# FDSSD.net
KiCad netlist of a schematic drawn in EAGLE
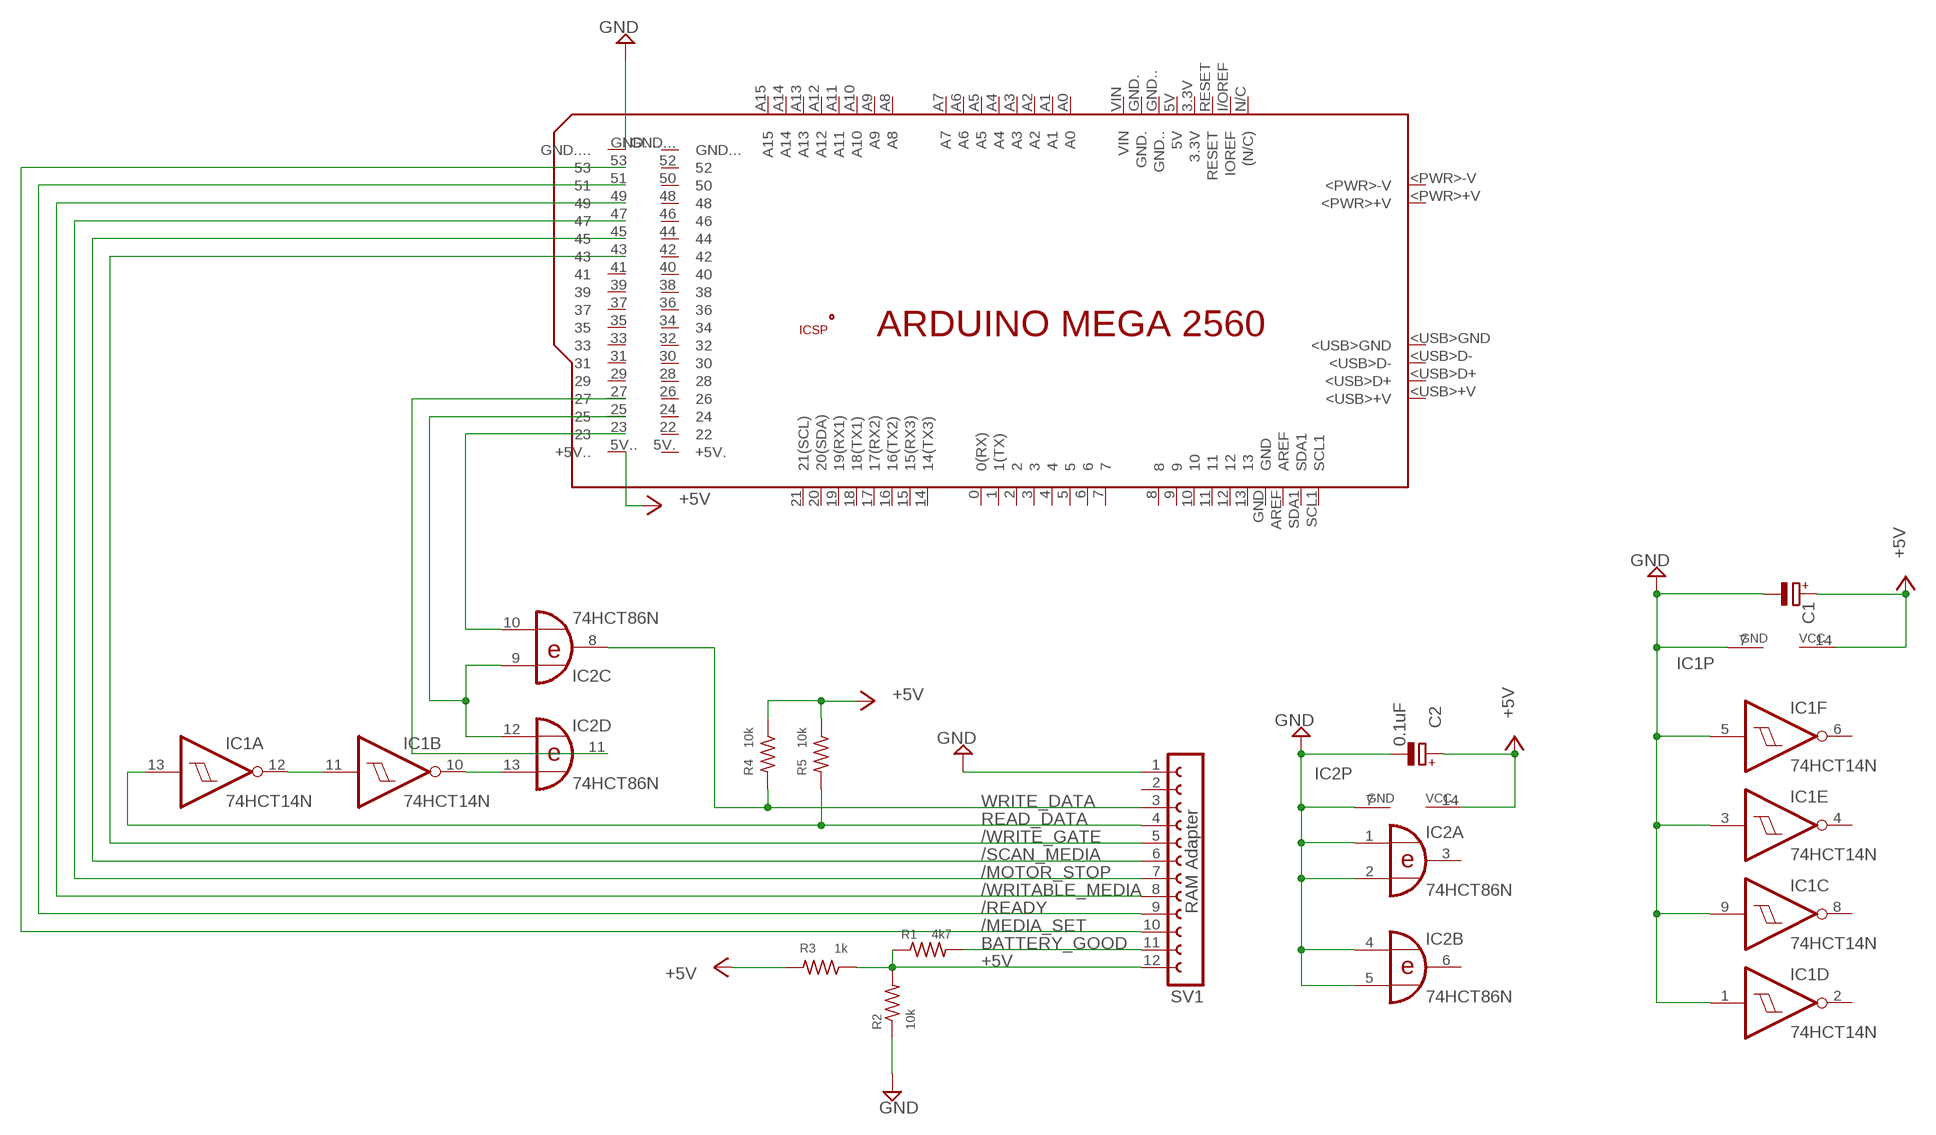
[diagram p0: schematic, sheet 1]

(export (version "E")
  (design (tool "Eeschema 10.0.6"))
  (components
    (comp (ref "C1")
      (value "CPOL-EUE2.5-5")
      (footprint "eagle-import:E2,5-5")
      (libsource (lib "eagle-import") (part "CPOL-EUE2.5-5"))
    )
    (comp (ref "C2")
      (value "0.1uF")
      (footprint "eagle-import:E2,5-5")
      (libsource (lib "eagle-import") (part "CPOL-EUE2.5-5"))
    )
    (comp (ref "IC1")
      (value "74HCT14N")
      (footprint "eagle-import:DIL14")
      (libsource (lib "eagle-import") (part "7414NHCT"))
    )
    (comp (ref "IC2")
      (value "74HCT86N")
      (footprint "eagle-import:DIL14")
      (libsource (lib "eagle-import") (part "7486NHCT"))
    )
    (comp (ref "PCB1")
      (value "ARDUINO_MEGA2560")
      (footprint "eagle-import:ARDUINO_MEGA2560")
      (libsource (lib "eagle-import") (part "ARDUINO_MEGA2560"))
    )
    (comp (ref "R1")
      (value "4k7")
      (footprint "eagle-import:0207_10")
      (libsource (lib "eagle-import") (part "R-US_0207/10"))
    )
    (comp (ref "R2")
      (value "10k")
      (footprint "eagle-import:0207_10")
      (libsource (lib "eagle-import") (part "R-US_0207/10"))
    )
    (comp (ref "R3")
      (value "1k")
      (footprint "eagle-import:0207_10")
      (libsource (lib "eagle-import") (part "R-US_0207/10"))
    )
    (comp (ref "R4")
      (value "10k")
      (footprint "eagle-import:0207_10")
      (libsource (lib "eagle-import") (part "R-US_0207/10"))
    )
    (comp (ref "R5")
      (value "10k")
      (footprint "eagle-import:0207_10")
      (libsource (lib "eagle-import") (part "R-US_0207/10"))
    )
    (comp (ref "SV1")
      (value "RAM Adapter")
      (footprint "eagle-import:FE12")
      (libsource (lib "eagle-import") (part "FE12-1"))
    )
  )
  (nets
    (net (code "1") (name "+5V") (class "Default")
      (node (ref "C1") (pin "+") (pinfunction "+_+") (pintype "passive"))
      (node (ref "C2") (pin "+") (pinfunction "+_+") (pintype "passive"))
      (node (ref "IC1") (pin "14") (pinfunction "VCC_14") (pintype "power_in"))
      (node (ref "IC2") (pin "14") (pinfunction "VCC_14") (pintype "power_in"))
      (node (ref "PCB1") (pin "5V..") (pinfunction "+5V.._5V..") (pintype "bidirectional"))
      (node (ref "R1") (pin "1") (pinfunction "1_1") (pintype "passive"))
      (node (ref "R2") (pin "2") (pinfunction "2_2") (pintype "passive"))
      (node (ref "R3") (pin "1") (pinfunction "1_1") (pintype "passive"))
      (node (ref "R3") (pin "2") (pinfunction "2_2") (pintype "passive"))
      (node (ref "R4") (pin "1") (pinfunction "1_1") (pintype "passive"))
      (node (ref "R5") (pin "1") (pinfunction "1_1") (pintype "passive"))
      (node (ref "SV1") (pin "12") (pinfunction "12_12") (pintype "passive"))
    )
    (net (code "2") (name "/BATTERY_GOOD") (class "Default")
      (node (ref "R1") (pin "2") (pinfunction "2_2") (pintype "passive"))
      (node (ref "SV1") (pin "11") (pinfunction "11_11") (pintype "passive"))
    )
    (net (code "3") (name "/READ_DATA") (class "Default")
      (node (ref "IC1") (pin "13") (pinfunction "I_13") (pintype "input"))
      (node (ref "R5") (pin "2") (pinfunction "2_2") (pintype "passive"))
      (node (ref "SV1") (pin "4") (pinfunction "4_4") (pintype "passive"))
    )
    (net (code "4") (name "/WRITE_DATA") (class "Default")
      (node (ref "IC2") (pin "8") (pinfunction "O_8") (pintype "output"))
      (node (ref "R4") (pin "2") (pinfunction "2_2") (pintype "passive"))
      (node (ref "SV1") (pin "3") (pinfunction "3_3") (pintype "passive"))
    )
    (net (code "5") (name "/{slash}MEDIA_SET") (class "Default")
      (node (ref "PCB1") (pin "53") (pinfunction "53_53") (pintype "bidirectional"))
      (node (ref "SV1") (pin "10") (pinfunction "10_10") (pintype "passive"))
    )
    (net (code "6") (name "/{slash}MOTOR_STOP") (class "Default")
      (node (ref "PCB1") (pin "47") (pinfunction "47_47") (pintype "bidirectional"))
      (node (ref "SV1") (pin "7") (pinfunction "7_7") (pintype "passive"))
    )
    (net (code "7") (name "/{slash}READY") (class "Default")
      (node (ref "PCB1") (pin "51") (pinfunction "51_51") (pintype "bidirectional"))
      (node (ref "SV1") (pin "9") (pinfunction "9_9") (pintype "passive"))
    )
    (net (code "8") (name "/{slash}SCAN_MEDIA") (class "Default")
      (node (ref "PCB1") (pin "45") (pinfunction "45_45") (pintype "bidirectional"))
      (node (ref "SV1") (pin "6") (pinfunction "6_6") (pintype "passive"))
    )
    (net (code "9") (name "/{slash}WRITABLE_MEDIA") (class "Default")
      (node (ref "PCB1") (pin "49") (pinfunction "49_49") (pintype "bidirectional"))
      (node (ref "SV1") (pin "8") (pinfunction "8_8") (pintype "passive"))
    )
    (net (code "10") (name "/{slash}WRITE_GATE") (class "Default")
      (node (ref "PCB1") (pin "43") (pinfunction "43_43") (pintype "bidirectional"))
      (node (ref "SV1") (pin "5") (pinfunction "5_5") (pintype "passive"))
    )
    (net (code "11") (name "GND") (class "Default")
      (node (ref "C1") (pin "-") (pinfunction "-_-") (pintype "passive"))
      (node (ref "C2") (pin "-") (pinfunction "-_-") (pintype "passive"))
      (node (ref "IC1") (pin "1") (pinfunction "I_1") (pintype "input"))
      (node (ref "IC1") (pin "3") (pinfunction "I_3") (pintype "input"))
      (node (ref "IC1") (pin "5") (pinfunction "I_5") (pintype "input"))
      (node (ref "IC1") (pin "7") (pinfunction "GND_7") (pintype "power_in"))
      (node (ref "IC1") (pin "9") (pinfunction "I_9") (pintype "input"))
      (node (ref "IC2") (pin "1") (pinfunction "I0_1") (pintype "input"))
      (node (ref "IC2") (pin "2") (pinfunction "I1_2") (pintype "input"))
      (node (ref "IC2") (pin "4") (pinfunction "I0_4") (pintype "input"))
      (node (ref "IC2") (pin "5") (pinfunction "I1_5") (pintype "input"))
      (node (ref "IC2") (pin "7") (pinfunction "GND_7") (pintype "power_in"))
      (node (ref "PCB1") (pin "GND....") (pinfunction "GND...._GND....") (pintype "bidirectional"))
      (node (ref "R2") (pin "1") (pinfunction "1_1") (pintype "passive"))
      (node (ref "SV1") (pin "1") (pinfunction "1_1") (pintype "passive"))
    )
    (net (code "12") (name "Net-(IC1A-O)") (class "Default")
      (node (ref "IC1") (pin "11") (pinfunction "I_11") (pintype "input"))
      (node (ref "IC1") (pin "12") (pinfunction "O_12") (pintype "output"))
    )
    (net (code "13") (name "Net-(IC1B-O)") (class "Default")
      (node (ref "IC1") (pin "10") (pinfunction "O_10") (pintype "output"))
      (node (ref "IC2") (pin "13") (pinfunction "I1_13") (pintype "input"))
    )
    (net (code "14") (name "Net-(IC2C-I0)") (class "Default")
      (node (ref "IC2") (pin "12") (pinfunction "I0_12") (pintype "input"))
      (node (ref "IC2") (pin "9") (pinfunction "I0_9") (pintype "input"))
      (node (ref "PCB1") (pin "25") (pinfunction "25_25") (pintype "bidirectional"))
    )
    (net (code "15") (name "Net-(IC2C-I1)") (class "Default")
      (node (ref "IC2") (pin "10") (pinfunction "I1_10") (pintype "input"))
      (node (ref "PCB1") (pin "23") (pinfunction "23_23") (pintype "bidirectional"))
    )
    (net (code "16") (name "Net-(IC2D-O)") (class "Default")
      (node (ref "IC2") (pin "11") (pinfunction "O_11") (pintype "output"))
      (node (ref "PCB1") (pin "27") (pinfunction "27_27") (pintype "bidirectional"))
    )
    (net (code "17") (name "unconnected-(IC1C-O-Pad8)") (class "Default")
      (node (ref "IC1") (pin "8") (pinfunction "O_8") (pintype "output"))
    )
    (net (code "18") (name "unconnected-(IC1D-O-Pad2)") (class "Default")
      (node (ref "IC1") (pin "2") (pinfunction "O_2") (pintype "output"))
    )
    (net (code "19") (name "unconnected-(IC1E-O-Pad4)") (class "Default")
      (node (ref "IC1") (pin "4") (pinfunction "O_4") (pintype "output"))
    )
    (net (code "20") (name "unconnected-(IC1F-O-Pad6)") (class "Default")
      (node (ref "IC1") (pin "6") (pinfunction "O_6") (pintype "output"))
    )
    (net (code "21") (name "unconnected-(IC2A-O-Pad3)") (class "Default")
      (node (ref "IC2") (pin "3") (pinfunction "O_3") (pintype "output"))
    )
    (net (code "22") (name "unconnected-(IC2B-O-Pad6)") (class "Default")
      (node (ref "IC2") (pin "6") (pinfunction "O_6") (pintype "output"))
    )
    (net (code "23") (name "unconnected-(PCB1-(N{slash}C)-PadN{slash}C)") (class "Default")
      (node (ref "PCB1") (pin "N/C") (pinfunction "(N/C)_N/C") (pintype "bidirectional"))
    )
    (net (code "24") (name "unconnected-(PCB1-+5V.-Pad5V.)") (class "Default")
      (node (ref "PCB1") (pin "5V.") (pinfunction "+5V._5V.") (pintype "bidirectional"))
    )
    (net (code "25") (name "unconnected-(PCB1-0(RX)-Pad0)") (class "Default")
      (node (ref "PCB1") (pin "0") (pinfunction "0(RX)_0") (pintype "bidirectional"))
    )
    (net (code "26") (name "unconnected-(PCB1-1(TX)-Pad1)") (class "Default")
      (node (ref "PCB1") (pin "1") (pinfunction "1(TX)_1") (pintype "bidirectional"))
    )
    (net (code "27") (name "unconnected-(PCB1-14(TX3)-Pad14)") (class "Default")
      (node (ref "PCB1") (pin "14") (pinfunction "14(TX3)_14") (pintype "bidirectional"))
    )
    (net (code "28") (name "unconnected-(PCB1-15(RX3)-Pad15)") (class "Default")
      (node (ref "PCB1") (pin "15") (pinfunction "15(RX3)_15") (pintype "bidirectional"))
    )
    (net (code "29") (name "unconnected-(PCB1-16(TX2)-Pad16)") (class "Default")
      (node (ref "PCB1") (pin "16") (pinfunction "16(TX2)_16") (pintype "bidirectional"))
    )
    (net (code "30") (name "unconnected-(PCB1-17(RX2)-Pad17)") (class "Default")
      (node (ref "PCB1") (pin "17") (pinfunction "17(RX2)_17") (pintype "bidirectional"))
    )
    (net (code "31") (name "unconnected-(PCB1-18(TX1)-Pad18)") (class "Default")
      (node (ref "PCB1") (pin "18") (pinfunction "18(TX1)_18") (pintype "bidirectional"))
    )
    (net (code "32") (name "unconnected-(PCB1-19(RX1)-Pad19)") (class "Default")
      (node (ref "PCB1") (pin "19") (pinfunction "19(RX1)_19") (pintype "bidirectional"))
    )
    (net (code "33") (name "unconnected-(PCB1-20(SDA)-Pad20)") (class "Default")
      (node (ref "PCB1") (pin "20") (pinfunction "20(SDA)_20") (pintype "bidirectional"))
    )
    (net (code "34") (name "unconnected-(PCB1-21(SCL)-Pad21)") (class "Default")
      (node (ref "PCB1") (pin "21") (pinfunction "21(SCL)_21") (pintype "bidirectional"))
    )
    (net (code "35") (name "unconnected-(PCB1-IOREF-PadI{slash}OREF)") (class "Default")
      (node (ref "PCB1") (pin "I/OREF") (pinfunction "IOREF_I/OREF") (pintype "bidirectional"))
    )
    (net (code "36") (name "unconnected-(PCB1-Pad+5V_)") (class "Default")
      (node (ref "PCB1") (pin "+5V_") (pinfunction "+5V__+5V_") (pintype "bidirectional"))
    )
    (net (code "37") (name "unconnected-(PCB1-Pad2)") (class "Default")
      (node (ref "PCB1") (pin "2") (pinfunction "2_2") (pintype "bidirectional"))
    )
    (net (code "38") (name "unconnected-(PCB1-Pad3)") (class "Default")
      (node (ref "PCB1") (pin "3") (pinfunction "3_3") (pintype "bidirectional"))
    )
    (net (code "39") (name "unconnected-(PCB1-Pad3.3V)") (class "Default")
      (node (ref "PCB1") (pin "3.3V") (pinfunction "3.3V_3.3V") (pintype "bidirectional"))
    )
    (net (code "40") (name "unconnected-(PCB1-Pad4)") (class "Default")
      (node (ref "PCB1") (pin "4") (pinfunction "4_4") (pintype "bidirectional"))
    )
    (net (code "41") (name "unconnected-(PCB1-Pad5)") (class "Default")
      (node (ref "PCB1") (pin "5") (pinfunction "5_5") (pintype "bidirectional"))
    )
    (net (code "42") (name "unconnected-(PCB1-Pad5V)") (class "Default")
      (node (ref "PCB1") (pin "5V") (pinfunction "5V_5V") (pintype "bidirectional"))
    )
    (net (code "43") (name "unconnected-(PCB1-Pad6)") (class "Default")
      (node (ref "PCB1") (pin "6") (pinfunction "6_6") (pintype "bidirectional"))
    )
    (net (code "44") (name "unconnected-(PCB1-Pad7)") (class "Default")
      (node (ref "PCB1") (pin "7") (pinfunction "7_7") (pintype "bidirectional"))
    )
    (net (code "45") (name "unconnected-(PCB1-Pad8)") (class "Default")
      (node (ref "PCB1") (pin "8") (pinfunction "8_8") (pintype "bidirectional"))
    )
    (net (code "46") (name "unconnected-(PCB1-Pad9)") (class "Default")
      (node (ref "PCB1") (pin "9") (pinfunction "9_9") (pintype "bidirectional"))
    )
    (net (code "47") (name "unconnected-(PCB1-Pad10)") (class "Default")
      (node (ref "PCB1") (pin "10") (pinfunction "10_10") (pintype "bidirectional"))
    )
    (net (code "48") (name "unconnected-(PCB1-Pad11)") (class "Default")
      (node (ref "PCB1") (pin "11") (pinfunction "11_11") (pintype "bidirectional"))
    )
    (net (code "49") (name "unconnected-(PCB1-Pad12)") (class "Default")
      (node (ref "PCB1") (pin "12") (pinfunction "12_12") (pintype "bidirectional"))
    )
    (net (code "50") (name "unconnected-(PCB1-Pad13)") (class "Default")
      (node (ref "PCB1") (pin "13") (pinfunction "13_13") (pintype "bidirectional"))
    )
    (net (code "51") (name "unconnected-(PCB1-Pad22)") (class "Default")
      (node (ref "PCB1") (pin "22") (pinfunction "22_22") (pintype "bidirectional"))
    )
    (net (code "52") (name "unconnected-(PCB1-Pad24)") (class "Default")
      (node (ref "PCB1") (pin "24") (pinfunction "24_24") (pintype "bidirectional"))
    )
    (net (code "53") (name "unconnected-(PCB1-Pad26)") (class "Default")
      (node (ref "PCB1") (pin "26") (pinfunction "26_26") (pintype "bidirectional"))
    )
    (net (code "54") (name "unconnected-(PCB1-Pad28)") (class "Default")
      (node (ref "PCB1") (pin "28") (pinfunction "28_28") (pintype "bidirectional"))
    )
    (net (code "55") (name "unconnected-(PCB1-Pad29)") (class "Default")
      (node (ref "PCB1") (pin "29") (pinfunction "29_29") (pintype "bidirectional"))
    )
    (net (code "56") (name "unconnected-(PCB1-Pad30)") (class "Default")
      (node (ref "PCB1") (pin "30") (pinfunction "30_30") (pintype "bidirectional"))
    )
    (net (code "57") (name "unconnected-(PCB1-Pad31)") (class "Default")
      (node (ref "PCB1") (pin "31") (pinfunction "31_31") (pintype "bidirectional"))
    )
    (net (code "58") (name "unconnected-(PCB1-Pad32)") (class "Default")
      (node (ref "PCB1") (pin "32") (pinfunction "32_32") (pintype "bidirectional"))
    )
    (net (code "59") (name "unconnected-(PCB1-Pad33)") (class "Default")
      (node (ref "PCB1") (pin "33") (pinfunction "33_33") (pintype "bidirectional"))
    )
    (net (code "60") (name "unconnected-(PCB1-Pad34)") (class "Default")
      (node (ref "PCB1") (pin "34") (pinfunction "34_34") (pintype "bidirectional"))
    )
    (net (code "61") (name "unconnected-(PCB1-Pad35)") (class "Default")
      (node (ref "PCB1") (pin "35") (pinfunction "35_35") (pintype "bidirectional"))
    )
    (net (code "62") (name "unconnected-(PCB1-Pad36)") (class "Default")
      (node (ref "PCB1") (pin "36") (pinfunction "36_36") (pintype "bidirectional"))
    )
    (net (code "63") (name "unconnected-(PCB1-Pad37)") (class "Default")
      (node (ref "PCB1") (pin "37") (pinfunction "37_37") (pintype "bidirectional"))
    )
    (net (code "64") (name "unconnected-(PCB1-Pad38)") (class "Default")
      (node (ref "PCB1") (pin "38") (pinfunction "38_38") (pintype "bidirectional"))
    )
    (net (code "65") (name "unconnected-(PCB1-Pad39)") (class "Default")
      (node (ref "PCB1") (pin "39") (pinfunction "39_39") (pintype "bidirectional"))
    )
    (net (code "66") (name "unconnected-(PCB1-Pad40)") (class "Default")
      (node (ref "PCB1") (pin "40") (pinfunction "40_40") (pintype "bidirectional"))
    )
    (net (code "67") (name "unconnected-(PCB1-Pad41)") (class "Default")
      (node (ref "PCB1") (pin "41") (pinfunction "41_41") (pintype "bidirectional"))
    )
    (net (code "68") (name "unconnected-(PCB1-Pad42)") (class "Default")
      (node (ref "PCB1") (pin "42") (pinfunction "42_42") (pintype "bidirectional"))
    )
    (net (code "69") (name "unconnected-(PCB1-Pad44)") (class "Default")
      (node (ref "PCB1") (pin "44") (pinfunction "44_44") (pintype "bidirectional"))
    )
    (net (code "70") (name "unconnected-(PCB1-Pad46)") (class "Default")
      (node (ref "PCB1") (pin "46") (pinfunction "46_46") (pintype "bidirectional"))
    )
    (net (code "71") (name "unconnected-(PCB1-Pad48)") (class "Default")
      (node (ref "PCB1") (pin "48") (pinfunction "48_48") (pintype "bidirectional"))
    )
    (net (code "72") (name "unconnected-(PCB1-Pad50)") (class "Default")
      (node (ref "PCB1") (pin "50") (pinfunction "50_50") (pintype "bidirectional"))
    )
    (net (code "73") (name "unconnected-(PCB1-Pad52)") (class "Default")
      (node (ref "PCB1") (pin "52") (pinfunction "52_52") (pintype "bidirectional"))
    )
    (net (code "74") (name "unconnected-(PCB1-Pad<PWR>+V)") (class "Default")
      (node (ref "PCB1") (pin "<PWR>+V") (pinfunction "<PWR>+V_<PWR>+V") (pintype "no_connect"))
    )
    (net (code "75") (name "unconnected-(PCB1-Pad<PWR>-V)") (class "Default")
      (node (ref "PCB1") (pin "<PWR>-V") (pinfunction "<PWR>-V_<PWR>-V") (pintype "no_connect"))
    )
    (net (code "76") (name "unconnected-(PCB1-Pad<USB>+V)") (class "Default")
      (node (ref "PCB1") (pin "<USB>+V") (pinfunction "<USB>+V_<USB>+V") (pintype "no_connect"))
    )
    (net (code "77") (name "unconnected-(PCB1-Pad<USB>D+)") (class "Default")
      (node (ref "PCB1") (pin "<USB>D+") (pinfunction "<USB>D+_<USB>D+") (pintype "no_connect"))
    )
    (net (code "78") (name "unconnected-(PCB1-Pad<USB>D-)") (class "Default")
      (node (ref "PCB1") (pin "<USB>D-") (pinfunction "<USB>D-_<USB>D-") (pintype "no_connect"))
    )
    (net (code "79") (name "unconnected-(PCB1-Pad<USB>GND)") (class "Default")
      (node (ref "PCB1") (pin "<USB>GND") (pinfunction "<USB>GND_<USB>GND") (pintype "no_connect"))
    )
    (net (code "80") (name "unconnected-(PCB1-PadA0)") (class "Default")
      (node (ref "PCB1") (pin "A0") (pinfunction "A0_A0") (pintype "bidirectional"))
    )
    (net (code "81") (name "unconnected-(PCB1-PadA1)") (class "Default")
      (node (ref "PCB1") (pin "A1") (pinfunction "A1_A1") (pintype "bidirectional"))
    )
    (net (code "82") (name "unconnected-(PCB1-PadA2)") (class "Default")
      (node (ref "PCB1") (pin "A2") (pinfunction "A2_A2") (pintype "bidirectional"))
    )
    (net (code "83") (name "unconnected-(PCB1-PadA3)") (class "Default")
      (node (ref "PCB1") (pin "A3") (pinfunction "A3_A3") (pintype "bidirectional"))
    )
    (net (code "84") (name "unconnected-(PCB1-PadA4)") (class "Default")
      (node (ref "PCB1") (pin "A4") (pinfunction "A4_A4") (pintype "bidirectional"))
    )
    (net (code "85") (name "unconnected-(PCB1-PadA5)") (class "Default")
      (node (ref "PCB1") (pin "A5") (pinfunction "A5_A5") (pintype "bidirectional"))
    )
    (net (code "86") (name "unconnected-(PCB1-PadA6)") (class "Default")
      (node (ref "PCB1") (pin "A6") (pinfunction "A6_A6") (pintype "bidirectional"))
    )
    (net (code "87") (name "unconnected-(PCB1-PadA7)") (class "Default")
      (node (ref "PCB1") (pin "A7") (pinfunction "A7_A7") (pintype "bidirectional"))
    )
    (net (code "88") (name "unconnected-(PCB1-PadA8)") (class "Default")
      (node (ref "PCB1") (pin "A8") (pinfunction "A8_A8") (pintype "bidirectional"))
    )
    (net (code "89") (name "unconnected-(PCB1-PadA9)") (class "Default")
      (node (ref "PCB1") (pin "A9") (pinfunction "A9_A9") (pintype "bidirectional"))
    )
    (net (code "90") (name "unconnected-(PCB1-PadA10)") (class "Default")
      (node (ref "PCB1") (pin "A10") (pinfunction "A10_A10") (pintype "bidirectional"))
    )
    (net (code "91") (name "unconnected-(PCB1-PadA11)") (class "Default")
      (node (ref "PCB1") (pin "A11") (pinfunction "A11_A11") (pintype "bidirectional"))
    )
    (net (code "92") (name "unconnected-(PCB1-PadA12)") (class "Default")
      (node (ref "PCB1") (pin "A12") (pinfunction "A12_A12") (pintype "bidirectional"))
    )
    (net (code "93") (name "unconnected-(PCB1-PadA13)") (class "Default")
      (node (ref "PCB1") (pin "A13") (pinfunction "A13_A13") (pintype "bidirectional"))
    )
    (net (code "94") (name "unconnected-(PCB1-PadA14)") (class "Default")
      (node (ref "PCB1") (pin "A14") (pinfunction "A14_A14") (pintype "bidirectional"))
    )
    (net (code "95") (name "unconnected-(PCB1-PadA15)") (class "Default")
      (node (ref "PCB1") (pin "A15") (pinfunction "A15_A15") (pintype "bidirectional"))
    )
    (net (code "96") (name "unconnected-(PCB1-PadAREF)") (class "Default")
      (node (ref "PCB1") (pin "AREF") (pinfunction "AREF_AREF") (pintype "bidirectional"))
    )
    (net (code "97") (name "unconnected-(PCB1-PadGND)") (class "Default")
      (node (ref "PCB1") (pin "GND") (pinfunction "GND_GND") (pintype "bidirectional"))
    )
    (net (code "98") (name "unconnected-(PCB1-PadGND.)") (class "Default")
      (node (ref "PCB1") (pin "GND.") (pinfunction "GND._GND.") (pintype "bidirectional"))
    )
    (net (code "99") (name "unconnected-(PCB1-PadGND..)") (class "Default")
      (node (ref "PCB1") (pin "GND..") (pinfunction "GND.._GND..") (pintype "bidirectional"))
    )
    (net (code "100") (name "unconnected-(PCB1-PadGND...)") (class "Default")
      (node (ref "PCB1") (pin "GND...") (pinfunction "GND..._GND...") (pintype "bidirectional"))
    )
    (net (code "101") (name "unconnected-(PCB1-PadGND__)") (class "Default")
      (node (ref "PCB1") (pin "GND__") (pinfunction "GND___GND__") (pintype "bidirectional"))
    )
    (net (code "102") (name "unconnected-(PCB1-PadMISO)") (class "Default")
      (node (ref "PCB1") (pin "MISO") (pinfunction "MISO_MISO") (pintype "bidirectional"))
    )
    (net (code "103") (name "unconnected-(PCB1-PadMOSI)") (class "Default")
      (node (ref "PCB1") (pin "MOSI") (pinfunction "MOSI_MOSI") (pintype "bidirectional"))
    )
    (net (code "104") (name "unconnected-(PCB1-PadRESET)") (class "Default")
      (node (ref "PCB1") (pin "RESET") (pinfunction "RESET_RESET") (pintype "bidirectional"))
    )
    (net (code "105") (name "unconnected-(PCB1-PadRESET.)") (class "Default")
      (node (ref "PCB1") (pin "RESET.") (pinfunction "RESET._RESET.") (pintype "bidirectional"))
    )
    (net (code "106") (name "unconnected-(PCB1-PadSCK)") (class "Default")
      (node (ref "PCB1") (pin "SCK") (pinfunction "SCK_SCK") (pintype "bidirectional"))
    )
    (net (code "107") (name "unconnected-(PCB1-PadSCL1)") (class "Default")
      (node (ref "PCB1") (pin "SCL1") (pinfunction "SCL1_SCL1") (pintype "bidirectional"))
    )
    (net (code "108") (name "unconnected-(PCB1-PadSDA1)") (class "Default")
      (node (ref "PCB1") (pin "SDA1") (pinfunction "SDA1_SDA1") (pintype "bidirectional"))
    )
    (net (code "109") (name "unconnected-(PCB1-PadVIN)") (class "Default")
      (node (ref "PCB1") (pin "VIN") (pinfunction "VIN_VIN") (pintype "bidirectional"))
    )
    (net (code "110") (name "unconnected-(SV1-Pad2)") (class "Default")
      (node (ref "SV1") (pin "2") (pinfunction "2_2") (pintype "passive"))
    )
  )
)
